# ne555n-monostable.net
KiCad netlist of a schematic drawn in EAGLE
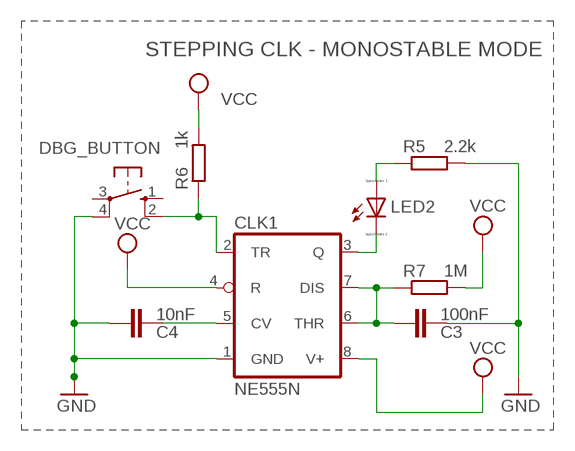
[diagram p0: schematic, sheet 1]

(export (version "E")
  (design (tool "Eeschema 10.0.6"))
  (components
    (comp (ref "C3")
      (value "100nF")
      (footprint "eagle-import:C025-050X050")
      (libsource (lib "eagle-import") (part "C-EU025-050X050"))
    )
    (comp (ref "C4")
      (value "10nF")
      (footprint "eagle-import:C025-050X050")
      (libsource (lib "eagle-import") (part "C-EU025-050X050"))
    )
    (comp (ref "CLK1")
      (value "NE555N")
      (footprint "eagle-import:DIL08")
      (libsource (lib "eagle-import") (part "555NNE"))
    )
    (comp (ref "DBG_BUTTON")
      (value "10-XX")
      (footprint "eagle-import:B3F-10XX")
      (fields (field (name "MPN") "B3F-1000"))
      (libsource (lib "eagle-import") (part "10-XX"))
    )
    (comp (ref "LED2")
      (value "LED_ELD260")
      (footprint "eagle-import:LED_LD260")
      (libsource (lib "eagle-import") (part "LED_ELD260"))
    )
    (comp (ref "R5")
      (value "2.2k")
      (footprint "eagle-import:0204_5")
      (libsource (lib "eagle-import") (part "R-EU_0204/5"))
    )
    (comp (ref "R6")
      (value "1k")
      (footprint "eagle-import:0204_5")
      (libsource (lib "eagle-import") (part "R-EU_0204/5"))
    )
    (comp (ref "R7")
      (value "1M")
      (footprint "eagle-import:0204_5")
      (libsource (lib "eagle-import") (part "R-EU_0204/5"))
    )
  )
  (nets
    (net (code "1") (name "GND") (class "Default")
      (node (ref "C3") (pin "1") (pinfunction "1_1") (pintype "passive"))
      (node (ref "C4") (pin "2") (pinfunction "2_2") (pintype "passive"))
      (node (ref "CLK1") (pin "1") (pinfunction "GND_1") (pintype "power_in"))
      (node (ref "DBG_BUTTON") (pin "4") (pinfunction "P1_4") (pintype "passive"))
      (node (ref "R5") (pin "2") (pinfunction "2_2") (pintype "passive"))
    )
    (net (code "2") (name "Net-(CLK1-CV)") (class "Default")
      (node (ref "C4") (pin "1") (pinfunction "1_1") (pintype "passive"))
      (node (ref "CLK1") (pin "5") (pinfunction "CV_5") (pintype "input"))
    )
    (net (code "3") (name "Net-(CLK1-DIS)") (class "Default")
      (node (ref "C3") (pin "2") (pinfunction "2_2") (pintype "passive"))
      (node (ref "CLK1") (pin "6") (pinfunction "THR_6") (pintype "input"))
      (node (ref "CLK1") (pin "7") (pinfunction "DIS_7") (pintype "input"))
      (node (ref "R7") (pin "1") (pinfunction "1_1") (pintype "passive"))
    )
    (net (code "4") (name "Net-(CLK1-Q)") (class "Default")
      (node (ref "CLK1") (pin "3") (pinfunction "Q_3") (pintype "output"))
      (node (ref "LED2") (pin "K") (pinfunction "C_K") (pintype "passive"))
    )
    (net (code "5") (name "Net-(CLK1-TR)") (class "Default")
      (node (ref "CLK1") (pin "2") (pinfunction "TR_2") (pintype "input"))
      (node (ref "DBG_BUTTON") (pin "2") (pinfunction "S1_2") (pintype "passive"))
      (node (ref "R6") (pin "1") (pinfunction "1_1") (pintype "passive"))
    )
    (net (code "6") (name "Net-(LED2-PadA)") (class "Default")
      (node (ref "LED2") (pin "A") (pinfunction "A_A") (pintype "passive"))
      (node (ref "R5") (pin "1") (pinfunction "1_1") (pintype "passive"))
    )
    (net (code "7") (name "VCC") (class "Default")
      (node (ref "CLK1") (pin "4") (pinfunction "R_4") (pintype "input"))
      (node (ref "CLK1") (pin "8") (pinfunction "V+_8") (pintype "power_in"))
      (node (ref "R6") (pin "2") (pinfunction "2_2") (pintype "passive"))
      (node (ref "R7") (pin "2") (pinfunction "2_2") (pintype "passive"))
    )
    (net (code "8") (name "unconnected-(DBG_BUTTON-P-Pad3)") (class "Default")
      (node (ref "DBG_BUTTON") (pin "3") (pinfunction "P_3") (pintype "passive"))
    )
    (net (code "9") (name "unconnected-(DBG_BUTTON-S-Pad1)") (class "Default")
      (node (ref "DBG_BUTTON") (pin "1") (pinfunction "S_1") (pintype "passive"))
    )
  )
)
